# PWM_Shield_SMD.net
KiCad netlist of a schematic drawn in EAGLE
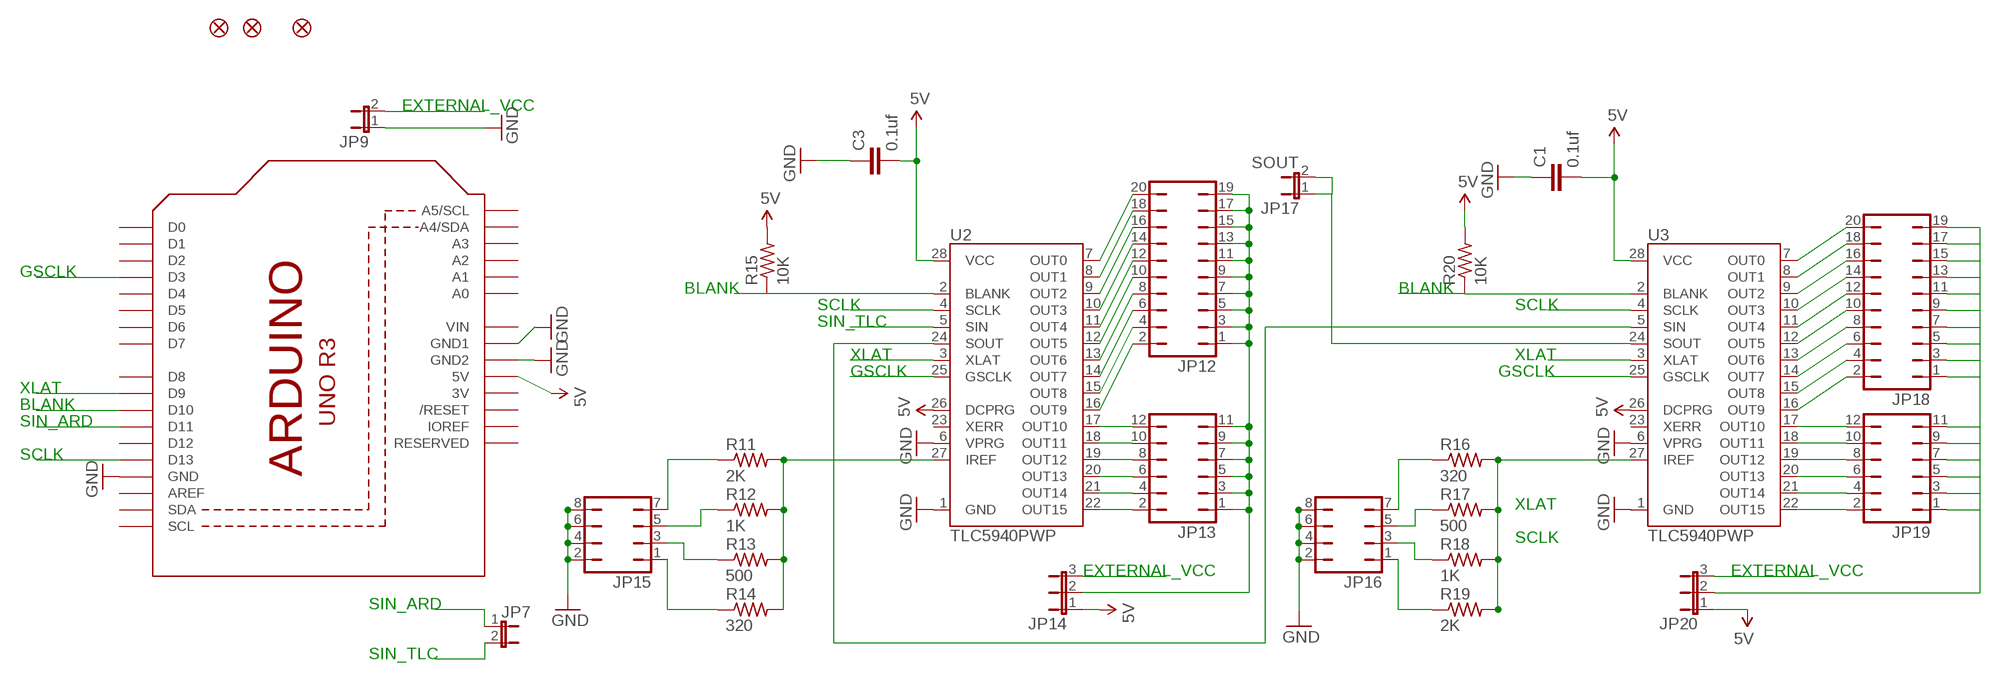
[diagram p0: schematic, sheet 1]

(export (version "E")
  (design (tool "Eeschema 10.0.6"))
  (components
    (comp (ref "C1")
      (value "0.1uf")
      (footprint "eagle-import:C0603")
      (libsource (lib "eagle-import") (part "C-EUC0603"))
    )
    (comp (ref "C3")
      (value "0.1uf")
      (footprint "eagle-import:C0603")
      (libsource (lib "eagle-import") (part "C-EUC0603"))
    )
    (comp (ref "JP1")
      (value "FIDUCIAL1.5X3")
      (footprint "eagle-import:FIDUCIAL-1.5X3")
      (libsource (lib "eagle-import") (part "FIDUCIAL1.5X3"))
    )
    (comp (ref "JP2")
      (value "FIDUCIAL1.5X3")
      (footprint "eagle-import:FIDUCIAL-1.5X3")
      (libsource (lib "eagle-import") (part "FIDUCIAL1.5X3"))
    )
    (comp (ref "JP3")
      (value "FIDUCIAL1.5X3")
      (footprint "eagle-import:FIDUCIAL-1.5X3")
      (libsource (lib "eagle-import") (part "FIDUCIAL1.5X3"))
    )
    (comp (ref "JP7")
      (value "JP1E")
      (footprint "eagle-import:JP1")
      (libsource (lib "eagle-import") (part "JP1E"))
    )
    (comp (ref "JP9")
      (value "JP1E")
      (footprint "eagle-import:JP1")
      (libsource (lib "eagle-import") (part "JP1E"))
    )
    (comp (ref "JP12")
      (value "JP10Q")
      (footprint "eagle-import:JP10Q")
      (libsource (lib "eagle-import") (part "JP10Q"))
    )
    (comp (ref "JP13")
      (value "JP6Q")
      (footprint "eagle-import:JP6Q")
      (libsource (lib "eagle-import") (part "JP6Q"))
    )
    (comp (ref "JP14")
      (value "JP2E")
      (footprint "eagle-import:JP2")
      (libsource (lib "eagle-import") (part "JP2E"))
    )
    (comp (ref "JP15")
      (value "JP4Q")
      (footprint "eagle-import:JP4Q")
      (libsource (lib "eagle-import") (part "JP4Q"))
    )
    (comp (ref "JP16")
      (value "JP4Q")
      (footprint "eagle-import:JP4Q")
      (libsource (lib "eagle-import") (part "JP4Q"))
    )
    (comp (ref "JP17")
      (value "SOUT")
      (footprint "eagle-import:JP1")
      (libsource (lib "eagle-import") (part "JP1E"))
    )
    (comp (ref "JP18")
      (value "JP10Q")
      (footprint "eagle-import:JP10Q")
      (libsource (lib "eagle-import") (part "JP10Q"))
    )
    (comp (ref "JP19")
      (value "JP6Q")
      (footprint "eagle-import:JP6Q")
      (libsource (lib "eagle-import") (part "JP6Q"))
    )
    (comp (ref "JP20")
      (value "JP2E")
      (footprint "eagle-import:JP2")
      (libsource (lib "eagle-import") (part "JP2E"))
    )
    (comp (ref "R11")
      (value "2K")
      (footprint "eagle-import:R0603")
      (libsource (lib "eagle-import") (part "R-US_R0603"))
    )
    (comp (ref "R12")
      (value "1K")
      (footprint "eagle-import:0204_7")
      (libsource (lib "eagle-import") (part "R-US_0204/7"))
    )
    (comp (ref "R13")
      (value "500")
      (footprint "eagle-import:0204_7")
      (libsource (lib "eagle-import") (part "R-US_0204/7"))
    )
    (comp (ref "R14")
      (value "320")
      (footprint "eagle-import:0204_7")
      (libsource (lib "eagle-import") (part "R-US_0204/7"))
    )
    (comp (ref "R15")
      (value "10K")
      (footprint "eagle-import:R0603")
      (libsource (lib "eagle-import") (part "R-US_R0603"))
    )
    (comp (ref "R16")
      (value "320")
      (footprint "eagle-import:0204_7")
      (libsource (lib "eagle-import") (part "R-US_0204/7"))
    )
    (comp (ref "R17")
      (value "500")
      (footprint "eagle-import:0204_7")
      (libsource (lib "eagle-import") (part "R-US_0204/7"))
    )
    (comp (ref "R18")
      (value "1K")
      (footprint "eagle-import:0204_7")
      (libsource (lib "eagle-import") (part "R-US_0204/7"))
    )
    (comp (ref "R19")
      (value "2K")
      (footprint "eagle-import:R0603")
      (libsource (lib "eagle-import") (part "R-US_R0603"))
    )
    (comp (ref "R20")
      (value "10K")
      (footprint "eagle-import:R0603")
      (libsource (lib "eagle-import") (part "R-US_R0603"))
    )
    (comp (ref "U1")
      (value "ARDUINOR3-DIMENSION")
      (footprint "eagle-import:ARDUINOR3")
      (libsource (lib "eagle-import") (part "ARDUINOR3-DIMENSION"))
    )
    (comp (ref "U2")
      (value "TLC5940PWP")
      (footprint "eagle-import:TSSOP28-GROUNDPAD")
      (libsource (lib "eagle-import") (part "TLC5940PWP"))
    )
    (comp (ref "U3")
      (value "TLC5940PWP")
      (footprint "eagle-import:TSSOP28-GROUNDPAD")
      (libsource (lib "eagle-import") (part "TLC5940PWP"))
    )
  )
  (nets
    (net (code "1") (name "/3V") (class "Default")
      (node (ref "U1") (pin "3V") (pinfunction "3V_3V") (pintype "power_in"))
    )
    (net (code "2") (name "/BLANK") (class "Default")
      (node (ref "R15") (pin "1") (pinfunction "1_1") (pintype "passive"))
      (node (ref "R20") (pin "1") (pinfunction "1_1") (pintype "passive"))
      (node (ref "U1") (pin "D10") (pinfunction "D10_D10") (pintype "bidirectional"))
      (node (ref "U2") (pin "2") (pinfunction "BLANK_2") (pintype "bidirectional"))
      (node (ref "U3") (pin "2") (pinfunction "BLANK_2") (pintype "bidirectional"))
    )
    (net (code "3") (name "/EXTERNAL_VCC") (class "Default")
      (node (ref "JP14") (pin "3") (pinfunction "3_3") (pintype "passive"))
      (node (ref "JP20") (pin "3") (pinfunction "3_3") (pintype "passive"))
      (node (ref "JP9") (pin "2") (pinfunction "2_2") (pintype "passive"))
    )
    (net (code "4") (name "/GSCLK") (class "Default")
      (node (ref "U1") (pin "D3") (pinfunction "D3_D3") (pintype "bidirectional"))
      (node (ref "U2") (pin "25") (pinfunction "GSCLK_25") (pintype "bidirectional"))
      (node (ref "U3") (pin "25") (pinfunction "GSCLK_25") (pintype "bidirectional"))
    )
    (net (code "5") (name "/SCLK") (class "Default")
      (node (ref "U1") (pin "D13") (pinfunction "D13_D13") (pintype "bidirectional"))
      (node (ref "U2") (pin "4") (pinfunction "SCLK_4") (pintype "bidirectional"))
      (node (ref "U3") (pin "4") (pinfunction "SCLK_4") (pintype "bidirectional"))
    )
    (net (code "6") (name "/SIN_ARD") (class "Default")
      (node (ref "JP7") (pin "1") (pinfunction "1_1") (pintype "passive"))
      (node (ref "U1") (pin "D11") (pinfunction "D11_D11") (pintype "bidirectional"))
    )
    (net (code "7") (name "/SIN_TLC") (class "Default")
      (node (ref "JP7") (pin "2") (pinfunction "2_2") (pintype "passive"))
      (node (ref "U2") (pin "5") (pinfunction "SIN_5") (pintype "bidirectional"))
    )
    (net (code "8") (name "/VIN") (class "Default")
      (node (ref "U1") (pin "VIN") (pinfunction "VIN_VIN") (pintype "power_in"))
    )
    (net (code "9") (name "/XLAT") (class "Default")
      (node (ref "U1") (pin "D9") (pinfunction "D9_D9") (pintype "bidirectional"))
      (node (ref "U2") (pin "3") (pinfunction "XLAT_3") (pintype "bidirectional"))
      (node (ref "U3") (pin "3") (pinfunction "XLAT_3") (pintype "bidirectional"))
    )
    (net (code "10") (name "5V") (class "Default")
      (node (ref "C1") (pin "2") (pinfunction "2_2") (pintype "passive"))
      (node (ref "C3") (pin "2") (pinfunction "2_2") (pintype "passive"))
      (node (ref "JP14") (pin "1") (pinfunction "1_1") (pintype "passive"))
      (node (ref "JP20") (pin "1") (pinfunction "1_1") (pintype "passive"))
      (node (ref "R15") (pin "2") (pinfunction "2_2") (pintype "passive"))
      (node (ref "R20") (pin "2") (pinfunction "2_2") (pintype "passive"))
      (node (ref "U1") (pin "5V") (pinfunction "5V_5V") (pintype "power_in"))
      (node (ref "U2") (pin "26") (pinfunction "DCPRG_26") (pintype "bidirectional"))
      (node (ref "U2") (pin "28") (pinfunction "VCC_28") (pintype "bidirectional"))
      (node (ref "U3") (pin "26") (pinfunction "DCPRG_26") (pintype "bidirectional"))
      (node (ref "U3") (pin "28") (pinfunction "VCC_28") (pintype "bidirectional"))
    )
    (net (code "11") (name "GND") (class "Default")
      (node (ref "C1") (pin "1") (pinfunction "1_1") (pintype "passive"))
      (node (ref "C3") (pin "1") (pinfunction "1_1") (pintype "passive"))
      (node (ref "JP15") (pin "2") (pinfunction "2_2") (pintype "passive"))
      (node (ref "JP15") (pin "4") (pinfunction "4_4") (pintype "passive"))
      (node (ref "JP15") (pin "6") (pinfunction "6_6") (pintype "passive"))
      (node (ref "JP15") (pin "8") (pinfunction "8_8") (pintype "passive"))
      (node (ref "JP16") (pin "2") (pinfunction "2_2") (pintype "passive"))
      (node (ref "JP16") (pin "4") (pinfunction "4_4") (pintype "passive"))
      (node (ref "JP16") (pin "6") (pinfunction "6_6") (pintype "passive"))
      (node (ref "JP16") (pin "8") (pinfunction "8_8") (pintype "passive"))
      (node (ref "JP9") (pin "1") (pinfunction "1_1") (pintype "passive"))
      (node (ref "U1") (pin "GND") (pinfunction "GND_GND") (pintype "power_in"))
      (node (ref "U1") (pin "GND1") (pinfunction "GND1_GND1") (pintype "power_in"))
      (node (ref "U1") (pin "GND2") (pinfunction "GND2_GND2") (pintype "power_in"))
      (node (ref "U2") (pin "1") (pinfunction "GND_1") (pintype "bidirectional"))
      (node (ref "U2") (pin "6") (pinfunction "VPRG_6") (pintype "bidirectional"))
      (node (ref "U3") (pin "1") (pinfunction "GND_1") (pintype "bidirectional"))
      (node (ref "U3") (pin "6") (pinfunction "VPRG_6") (pintype "bidirectional"))
    )
    (net (code "12") (name "Net-(JP12-Pad1)") (class "Default")
      (node (ref "JP12") (pin "1") (pinfunction "1_1") (pintype "passive"))
      (node (ref "JP12") (pin "11") (pinfunction "11_11") (pintype "passive"))
      (node (ref "JP12") (pin "13") (pinfunction "13_13") (pintype "passive"))
      (node (ref "JP12") (pin "15") (pinfunction "15_15") (pintype "passive"))
      (node (ref "JP12") (pin "17") (pinfunction "17_17") (pintype "passive"))
      (node (ref "JP12") (pin "19") (pinfunction "19_19") (pintype "passive"))
      (node (ref "JP12") (pin "3") (pinfunction "3_3") (pintype "passive"))
      (node (ref "JP12") (pin "5") (pinfunction "5_5") (pintype "passive"))
      (node (ref "JP12") (pin "7") (pinfunction "7_7") (pintype "passive"))
      (node (ref "JP12") (pin "9") (pinfunction "9_9") (pintype "passive"))
      (node (ref "JP13") (pin "1") (pinfunction "1_1") (pintype "passive"))
      (node (ref "JP13") (pin "11") (pinfunction "11_11") (pintype "passive"))
      (node (ref "JP13") (pin "3") (pinfunction "3_3") (pintype "passive"))
      (node (ref "JP13") (pin "5") (pinfunction "5_5") (pintype "passive"))
      (node (ref "JP13") (pin "7") (pinfunction "7_7") (pintype "passive"))
      (node (ref "JP13") (pin "9") (pinfunction "9_9") (pintype "passive"))
      (node (ref "JP14") (pin "2") (pinfunction "2_2") (pintype "passive"))
    )
    (net (code "13") (name "Net-(JP15-Pad1)") (class "Default")
      (node (ref "JP15") (pin "1") (pinfunction "1_1") (pintype "passive"))
      (node (ref "R14") (pin "1") (pinfunction "1_1") (pintype "passive"))
    )
    (net (code "14") (name "Net-(JP15-Pad3)") (class "Default")
      (node (ref "JP15") (pin "3") (pinfunction "3_3") (pintype "passive"))
      (node (ref "R13") (pin "1") (pinfunction "1_1") (pintype "passive"))
    )
    (net (code "15") (name "Net-(JP15-Pad5)") (class "Default")
      (node (ref "JP15") (pin "5") (pinfunction "5_5") (pintype "passive"))
      (node (ref "R12") (pin "1") (pinfunction "1_1") (pintype "passive"))
    )
    (net (code "16") (name "Net-(JP15-Pad7)") (class "Default")
      (node (ref "JP15") (pin "7") (pinfunction "7_7") (pintype "passive"))
      (node (ref "R11") (pin "1") (pinfunction "1_1") (pintype "passive"))
    )
    (net (code "17") (name "Net-(JP16-Pad1)") (class "Default")
      (node (ref "JP16") (pin "1") (pinfunction "1_1") (pintype "passive"))
      (node (ref "R19") (pin "1") (pinfunction "1_1") (pintype "passive"))
    )
    (net (code "18") (name "Net-(JP16-Pad3)") (class "Default")
      (node (ref "JP16") (pin "3") (pinfunction "3_3") (pintype "passive"))
      (node (ref "R18") (pin "1") (pinfunction "1_1") (pintype "passive"))
    )
    (net (code "19") (name "Net-(JP16-Pad5)") (class "Default")
      (node (ref "JP16") (pin "5") (pinfunction "5_5") (pintype "passive"))
      (node (ref "R17") (pin "1") (pinfunction "1_1") (pintype "passive"))
    )
    (net (code "20") (name "Net-(JP16-Pad7)") (class "Default")
      (node (ref "JP16") (pin "7") (pinfunction "7_7") (pintype "passive"))
      (node (ref "R16") (pin "1") (pinfunction "1_1") (pintype "passive"))
    )
    (net (code "21") (name "Net-(JP18-Pad1)") (class "Default")
      (node (ref "JP18") (pin "1") (pinfunction "1_1") (pintype "passive"))
      (node (ref "JP18") (pin "11") (pinfunction "11_11") (pintype "passive"))
      (node (ref "JP18") (pin "13") (pinfunction "13_13") (pintype "passive"))
      (node (ref "JP18") (pin "15") (pinfunction "15_15") (pintype "passive"))
      (node (ref "JP18") (pin "17") (pinfunction "17_17") (pintype "passive"))
      (node (ref "JP18") (pin "19") (pinfunction "19_19") (pintype "passive"))
      (node (ref "JP18") (pin "3") (pinfunction "3_3") (pintype "passive"))
      (node (ref "JP18") (pin "5") (pinfunction "5_5") (pintype "passive"))
      (node (ref "JP18") (pin "7") (pinfunction "7_7") (pintype "passive"))
      (node (ref "JP18") (pin "9") (pinfunction "9_9") (pintype "passive"))
      (node (ref "JP19") (pin "1") (pinfunction "1_1") (pintype "passive"))
      (node (ref "JP19") (pin "11") (pinfunction "11_11") (pintype "passive"))
      (node (ref "JP19") (pin "3") (pinfunction "3_3") (pintype "passive"))
      (node (ref "JP19") (pin "5") (pinfunction "5_5") (pintype "passive"))
      (node (ref "JP19") (pin "7") (pinfunction "7_7") (pintype "passive"))
      (node (ref "JP19") (pin "9") (pinfunction "9_9") (pintype "passive"))
      (node (ref "JP20") (pin "2") (pinfunction "2_2") (pintype "passive"))
    )
    (net (code "22") (name "Net-(U2-IREF)") (class "Default")
      (node (ref "R11") (pin "2") (pinfunction "2_2") (pintype "passive"))
      (node (ref "R12") (pin "2") (pinfunction "2_2") (pintype "passive"))
      (node (ref "R13") (pin "2") (pinfunction "2_2") (pintype "passive"))
      (node (ref "R14") (pin "2") (pinfunction "2_2") (pintype "passive"))
      (node (ref "U2") (pin "27") (pinfunction "IREF_27") (pintype "bidirectional"))
    )
    (net (code "23") (name "Net-(U2-OUT0)") (class "Default")
      (node (ref "JP12") (pin "20") (pinfunction "20_20") (pintype "passive"))
      (node (ref "U2") (pin "7") (pinfunction "OUT0_7") (pintype "bidirectional"))
    )
    (net (code "24") (name "Net-(U2-OUT1)") (class "Default")
      (node (ref "JP12") (pin "18") (pinfunction "18_18") (pintype "passive"))
      (node (ref "U2") (pin "8") (pinfunction "OUT1_8") (pintype "bidirectional"))
    )
    (net (code "25") (name "Net-(U2-OUT2)") (class "Default")
      (node (ref "JP12") (pin "16") (pinfunction "16_16") (pintype "passive"))
      (node (ref "U2") (pin "9") (pinfunction "OUT2_9") (pintype "bidirectional"))
    )
    (net (code "26") (name "Net-(U2-OUT3)") (class "Default")
      (node (ref "JP12") (pin "14") (pinfunction "14_14") (pintype "passive"))
      (node (ref "U2") (pin "10") (pinfunction "OUT3_10") (pintype "bidirectional"))
    )
    (net (code "27") (name "Net-(U2-OUT4)") (class "Default")
      (node (ref "JP12") (pin "12") (pinfunction "12_12") (pintype "passive"))
      (node (ref "U2") (pin "11") (pinfunction "OUT4_11") (pintype "bidirectional"))
    )
    (net (code "28") (name "Net-(U2-OUT5)") (class "Default")
      (node (ref "JP12") (pin "10") (pinfunction "10_10") (pintype "passive"))
      (node (ref "U2") (pin "12") (pinfunction "OUT5_12") (pintype "bidirectional"))
    )
    (net (code "29") (name "Net-(U2-OUT6)") (class "Default")
      (node (ref "JP12") (pin "8") (pinfunction "8_8") (pintype "passive"))
      (node (ref "U2") (pin "13") (pinfunction "OUT6_13") (pintype "bidirectional"))
    )
    (net (code "30") (name "Net-(U2-OUT7)") (class "Default")
      (node (ref "JP12") (pin "6") (pinfunction "6_6") (pintype "passive"))
      (node (ref "U2") (pin "14") (pinfunction "OUT7_14") (pintype "bidirectional"))
    )
    (net (code "31") (name "Net-(U2-OUT8)") (class "Default")
      (node (ref "JP12") (pin "4") (pinfunction "4_4") (pintype "passive"))
      (node (ref "U2") (pin "15") (pinfunction "OUT8_15") (pintype "bidirectional"))
    )
    (net (code "32") (name "Net-(U2-OUT9)") (class "Default")
      (node (ref "JP12") (pin "2") (pinfunction "2_2") (pintype "passive"))
      (node (ref "U2") (pin "16") (pinfunction "OUT9_16") (pintype "bidirectional"))
    )
    (net (code "33") (name "Net-(U2-OUT10)") (class "Default")
      (node (ref "JP13") (pin "12") (pinfunction "12_12") (pintype "passive"))
      (node (ref "U2") (pin "17") (pinfunction "OUT10_17") (pintype "bidirectional"))
    )
    (net (code "34") (name "Net-(U2-OUT11)") (class "Default")
      (node (ref "JP13") (pin "10") (pinfunction "10_10") (pintype "passive"))
      (node (ref "U2") (pin "18") (pinfunction "OUT11_18") (pintype "bidirectional"))
    )
    (net (code "35") (name "Net-(U2-OUT12)") (class "Default")
      (node (ref "JP13") (pin "8") (pinfunction "8_8") (pintype "passive"))
      (node (ref "U2") (pin "19") (pinfunction "OUT12_19") (pintype "bidirectional"))
    )
    (net (code "36") (name "Net-(U2-OUT13)") (class "Default")
      (node (ref "JP13") (pin "6") (pinfunction "6_6") (pintype "passive"))
      (node (ref "U2") (pin "20") (pinfunction "OUT13_20") (pintype "bidirectional"))
    )
    (net (code "37") (name "Net-(U2-OUT14)") (class "Default")
      (node (ref "JP13") (pin "4") (pinfunction "4_4") (pintype "passive"))
      (node (ref "U2") (pin "21") (pinfunction "OUT14_21") (pintype "bidirectional"))
    )
    (net (code "38") (name "Net-(U2-OUT15)") (class "Default")
      (node (ref "JP13") (pin "2") (pinfunction "2_2") (pintype "passive"))
      (node (ref "U2") (pin "22") (pinfunction "OUT15_22") (pintype "bidirectional"))
    )
    (net (code "39") (name "Net-(U2-SOUT)") (class "Default")
      (node (ref "U2") (pin "24") (pinfunction "SOUT_24") (pintype "bidirectional"))
      (node (ref "U3") (pin "5") (pinfunction "SIN_5") (pintype "bidirectional"))
    )
    (net (code "40") (name "Net-(U3-IREF)") (class "Default")
      (node (ref "R16") (pin "2") (pinfunction "2_2") (pintype "passive"))
      (node (ref "R17") (pin "2") (pinfunction "2_2") (pintype "passive"))
      (node (ref "R18") (pin "2") (pinfunction "2_2") (pintype "passive"))
      (node (ref "R19") (pin "2") (pinfunction "2_2") (pintype "passive"))
      (node (ref "U3") (pin "27") (pinfunction "IREF_27") (pintype "bidirectional"))
    )
    (net (code "41") (name "Net-(U3-OUT0)") (class "Default")
      (node (ref "JP18") (pin "20") (pinfunction "20_20") (pintype "passive"))
      (node (ref "U3") (pin "7") (pinfunction "OUT0_7") (pintype "bidirectional"))
    )
    (net (code "42") (name "Net-(U3-OUT1)") (class "Default")
      (node (ref "JP18") (pin "18") (pinfunction "18_18") (pintype "passive"))
      (node (ref "U3") (pin "8") (pinfunction "OUT1_8") (pintype "bidirectional"))
    )
    (net (code "43") (name "Net-(U3-OUT2)") (class "Default")
      (node (ref "JP18") (pin "16") (pinfunction "16_16") (pintype "passive"))
      (node (ref "U3") (pin "9") (pinfunction "OUT2_9") (pintype "bidirectional"))
    )
    (net (code "44") (name "Net-(U3-OUT3)") (class "Default")
      (node (ref "JP18") (pin "14") (pinfunction "14_14") (pintype "passive"))
      (node (ref "U3") (pin "10") (pinfunction "OUT3_10") (pintype "bidirectional"))
    )
    (net (code "45") (name "Net-(U3-OUT4)") (class "Default")
      (node (ref "JP18") (pin "12") (pinfunction "12_12") (pintype "passive"))
      (node (ref "U3") (pin "11") (pinfunction "OUT4_11") (pintype "bidirectional"))
    )
    (net (code "46") (name "Net-(U3-OUT5)") (class "Default")
      (node (ref "JP18") (pin "10") (pinfunction "10_10") (pintype "passive"))
      (node (ref "U3") (pin "12") (pinfunction "OUT5_12") (pintype "bidirectional"))
    )
    (net (code "47") (name "Net-(U3-OUT6)") (class "Default")
      (node (ref "JP18") (pin "8") (pinfunction "8_8") (pintype "passive"))
      (node (ref "U3") (pin "13") (pinfunction "OUT6_13") (pintype "bidirectional"))
    )
    (net (code "48") (name "Net-(U3-OUT7)") (class "Default")
      (node (ref "JP18") (pin "6") (pinfunction "6_6") (pintype "passive"))
      (node (ref "U3") (pin "14") (pinfunction "OUT7_14") (pintype "bidirectional"))
    )
    (net (code "49") (name "Net-(U3-OUT8)") (class "Default")
      (node (ref "JP18") (pin "4") (pinfunction "4_4") (pintype "passive"))
      (node (ref "U3") (pin "15") (pinfunction "OUT8_15") (pintype "bidirectional"))
    )
    (net (code "50") (name "Net-(U3-OUT9)") (class "Default")
      (node (ref "JP18") (pin "2") (pinfunction "2_2") (pintype "passive"))
      (node (ref "U3") (pin "16") (pinfunction "OUT9_16") (pintype "bidirectional"))
    )
    (net (code "51") (name "Net-(U3-OUT10)") (class "Default")
      (node (ref "JP19") (pin "12") (pinfunction "12_12") (pintype "passive"))
      (node (ref "U3") (pin "17") (pinfunction "OUT10_17") (pintype "bidirectional"))
    )
    (net (code "52") (name "Net-(U3-OUT11)") (class "Default")
      (node (ref "JP19") (pin "10") (pinfunction "10_10") (pintype "passive"))
      (node (ref "U3") (pin "18") (pinfunction "OUT11_18") (pintype "bidirectional"))
    )
    (net (code "53") (name "Net-(U3-OUT12)") (class "Default")
      (node (ref "JP19") (pin "8") (pinfunction "8_8") (pintype "passive"))
      (node (ref "U3") (pin "19") (pinfunction "OUT12_19") (pintype "bidirectional"))
    )
    (net (code "54") (name "Net-(U3-OUT13)") (class "Default")
      (node (ref "JP19") (pin "6") (pinfunction "6_6") (pintype "passive"))
      (node (ref "U3") (pin "20") (pinfunction "OUT13_20") (pintype "bidirectional"))
    )
    (net (code "55") (name "Net-(U3-OUT14)") (class "Default")
      (node (ref "JP19") (pin "4") (pinfunction "4_4") (pintype "passive"))
      (node (ref "U3") (pin "21") (pinfunction "OUT14_21") (pintype "bidirectional"))
    )
    (net (code "56") (name "Net-(U3-OUT15)") (class "Default")
      (node (ref "JP19") (pin "2") (pinfunction "2_2") (pintype "passive"))
      (node (ref "U3") (pin "22") (pinfunction "OUT15_22") (pintype "bidirectional"))
    )
    (net (code "57") (name "Net-(U3-SOUT)") (class "Default")
      (node (ref "JP17") (pin "1") (pinfunction "1_1") (pintype "passive"))
      (node (ref "JP17") (pin "2") (pinfunction "2_2") (pintype "passive"))
      (node (ref "U3") (pin "24") (pinfunction "SOUT_24") (pintype "bidirectional"))
    )
    (net (code "58") (name "unconnected-(U1-A4{slash}SDA-PadA4)") (class "Default")
      (node (ref "U1") (pin "A4") (pinfunction "A4/SDA_A4") (pintype "bidirectional"))
    )
    (net (code "59") (name "unconnected-(U1-A5{slash}SCL-PadA5)") (class "Default")
      (node (ref "U1") (pin "A5") (pinfunction "A5/SCL_A5") (pintype "bidirectional"))
    )
    (net (code "60") (name "unconnected-(U1-PadA0)") (class "Default")
      (node (ref "U1") (pin "A0") (pinfunction "A0_A0") (pintype "bidirectional"))
    )
    (net (code "61") (name "unconnected-(U1-PadA1)") (class "Default")
      (node (ref "U1") (pin "A1") (pinfunction "A1_A1") (pintype "bidirectional"))
    )
    (net (code "62") (name "unconnected-(U1-PadA2)") (class "Default")
      (node (ref "U1") (pin "A2") (pinfunction "A2_A2") (pintype "bidirectional"))
    )
    (net (code "63") (name "unconnected-(U1-PadA3)") (class "Default")
      (node (ref "U1") (pin "A3") (pinfunction "A3_A3") (pintype "bidirectional"))
    )
    (net (code "64") (name "unconnected-(U1-PadAREF)") (class "Default")
      (node (ref "U1") (pin "AREF") (pinfunction "AREF_AREF") (pintype "bidirectional"))
    )
    (net (code "65") (name "unconnected-(U1-PadD0)") (class "Default")
      (node (ref "U1") (pin "D0") (pinfunction "D0_D0") (pintype "bidirectional"))
    )
    (net (code "66") (name "unconnected-(U1-PadD1)") (class "Default")
      (node (ref "U1") (pin "D1") (pinfunction "D1_D1") (pintype "bidirectional"))
    )
    (net (code "67") (name "unconnected-(U1-PadD2)") (class "Default")
      (node (ref "U1") (pin "D2") (pinfunction "D2_D2") (pintype "bidirectional"))
    )
    (net (code "68") (name "unconnected-(U1-PadD4)") (class "Default")
      (node (ref "U1") (pin "D4") (pinfunction "D4_D4") (pintype "bidirectional"))
    )
    (net (code "69") (name "unconnected-(U1-PadD5)") (class "Default")
      (node (ref "U1") (pin "D5") (pinfunction "D5_D5") (pintype "bidirectional"))
    )
    (net (code "70") (name "unconnected-(U1-PadD6)") (class "Default")
      (node (ref "U1") (pin "D6") (pinfunction "D6_D6") (pintype "bidirectional"))
    )
    (net (code "71") (name "unconnected-(U1-PadD7)") (class "Default")
      (node (ref "U1") (pin "D7") (pinfunction "D7_D7") (pintype "bidirectional"))
    )
    (net (code "72") (name "unconnected-(U1-PadD8)") (class "Default")
      (node (ref "U1") (pin "D8") (pinfunction "D8_D8") (pintype "bidirectional"))
    )
    (net (code "73") (name "unconnected-(U1-PadD12)") (class "Default")
      (node (ref "U1") (pin "D12") (pinfunction "D12_D12") (pintype "bidirectional"))
    )
    (net (code "74") (name "unconnected-(U1-PadIOREF)") (class "Default")
      (node (ref "U1") (pin "IOREF") (pinfunction "IOREF_IOREF") (pintype "output"))
    )
    (net (code "75") (name "unconnected-(U1-PadRESERVED)") (class "Default")
      (node (ref "U1") (pin "RESERVED") (pinfunction "RESERVED_RESERVED") (pintype "no_connect"))
    )
    (net (code "76") (name "unconnected-(U1-PadSCL)") (class "Default")
      (node (ref "U1") (pin "SCL") (pinfunction "SCL_SCL") (pintype "bidirectional"))
    )
    (net (code "77") (name "unconnected-(U1-PadSDA)") (class "Default")
      (node (ref "U1") (pin "SDA") (pinfunction "SDA_SDA") (pintype "bidirectional"))
    )
    (net (code "78") (name "unconnected-(U1-{slash}RESET-PadRESET)") (class "Default")
      (node (ref "U1") (pin "RESET") (pinfunction "/RESET_RESET") (pintype "bidirectional"))
    )
    (net (code "79") (name "unconnected-(U2-XERR-Pad23)") (class "Default")
      (node (ref "U2") (pin "23") (pinfunction "XERR_23") (pintype "bidirectional"))
    )
    (net (code "80") (name "unconnected-(U3-XERR-Pad23)") (class "Default")
      (node (ref "U3") (pin "23") (pinfunction "XERR_23") (pintype "bidirectional"))
    )
  )
)
